# MCU063B_EtherNET.net
KiCad netlist of a schematic drawn in Altium Designer
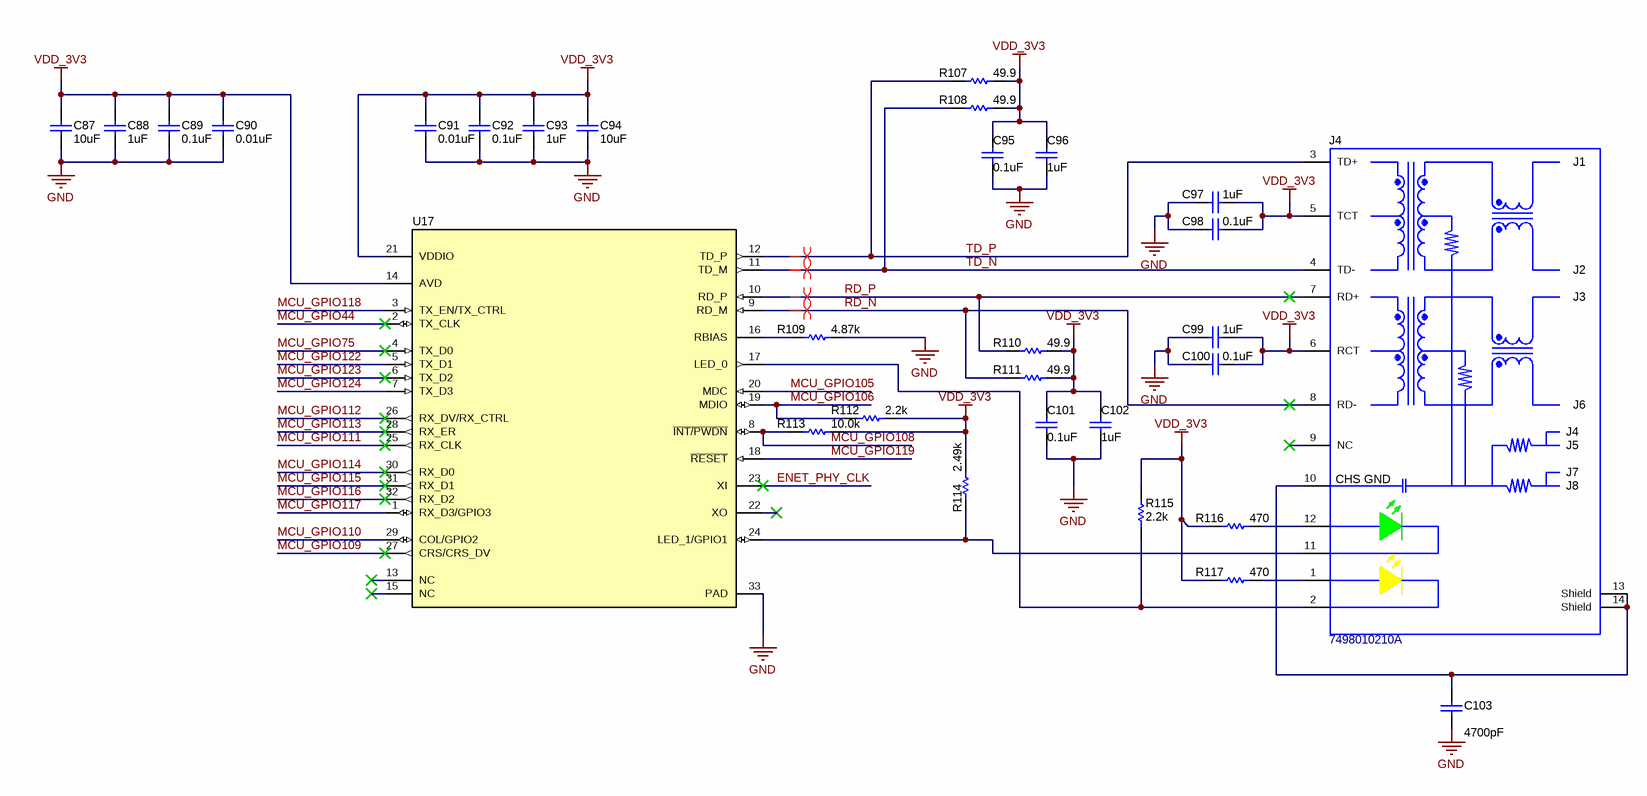
[diagram p0: MCU063B_EtherNET.SchDoc]

(export (version "E")
  (design (tool "Eeschema 10.0.6"))
  (components
    (comp (ref "C87")
      (value "CL05A106MQ5NUNC")
      (footprint "0402")
      (description "CAP, CERM, 10 uF, 6.3 V, +/- 20%, X5R, 0402")
      (fields
        (field (name "MANUFACTURER") "Samsung Electro-Mechanics")
        (field (name "VALUEDISPLAYED") "10uF")
        (field (name "PUBLISHER") "Texas Instruments")
      )
      (libsource (lib "Altium Vault - TI") (part "Capacitor"))
    )
    (comp (ref "C88")
      (value "EMK105BJ105KVHF")
      (footprint "0402")
      (description "CAP, CERM, 1 uF, 16 V, +/- 10%, X5R, 0402")
      (fields
        (field (name "MANUFACTURER") "Taiyo Yuden")
        (field (name "VALUEDISPLAYED") "1uF")
        (field (name "PUBLISHER") "Texas Instruments")
      )
      (libsource (lib "Altium Vault - TI") (part "Capacitor"))
    )
    (comp (ref "C89")
      (value "LMK105BJ104KV-F")
      (footprint "0402")
      (description "CAP, CERM, 0.1 uF, 10 V,+/- 10%, X5R, 0402")
      (fields
        (field (name "MANUFACTURER") "Taiyo Yuden")
        (field (name "VALUEDISPLAYED") "0.1uF")
        (field (name "PUBLISHER") "Texas Instruments")
      )
      (libsource (lib "Altium Vault - TI") (part "Capacitor"))
    )
    (comp (ref "C90")
      (value "885012205031")
      (footprint "0402")
      (description "CAP, CERM, 0.01 uF, 16 V, +/- 10%, X7R, 0402")
      (fields
        (field (name "MANUFACTURER") "Wurth Elektronik")
        (field (name "VALUEDISPLAYED") "0.01uF")
        (field (name "PUBLISHER") "Texas Instruments")
      )
      (libsource (lib "Altium Vault - TI") (part "Capacitor"))
    )
    (comp (ref "C91")
      (value "885012205031")
      (footprint "0402")
      (description "CAP, CERM, 0.01 uF, 16 V, +/- 10%, X7R, 0402")
      (fields
        (field (name "MANUFACTURER") "Wurth Elektronik")
        (field (name "VALUEDISPLAYED") "0.01uF")
        (field (name "PUBLISHER") "Texas Instruments")
      )
      (libsource (lib "Altium Vault - TI") (part "Capacitor"))
    )
    (comp (ref "C92")
      (value "LMK105BJ104KV-F")
      (footprint "0402")
      (description "CAP, CERM, 0.1 uF, 10 V,+/- 10%, X5R, 0402")
      (fields
        (field (name "MANUFACTURER") "Taiyo Yuden")
        (field (name "VALUEDISPLAYED") "0.1uF")
        (field (name "PUBLISHER") "Texas Instruments")
      )
      (libsource (lib "Altium Vault - TI") (part "Capacitor"))
    )
    (comp (ref "C93")
      (value "EMK105BJ105KVHF")
      (footprint "0402")
      (description "CAP, CERM, 1 uF, 16 V, +/- 10%, X5R, 0402")
      (fields
        (field (name "MANUFACTURER") "Taiyo Yuden")
        (field (name "VALUEDISPLAYED") "1uF")
        (field (name "PUBLISHER") "Texas Instruments")
      )
      (libsource (lib "Altium Vault - TI") (part "Capacitor"))
    )
    (comp (ref "C94")
      (value "CL05A106MQ5NUNC")
      (footprint "0402")
      (description "CAP, CERM, 10 uF, 6.3 V, +/- 20%, X5R, 0402")
      (fields
        (field (name "MANUFACTURER") "Samsung Electro-Mechanics")
        (field (name "VALUEDISPLAYED") "10uF")
        (field (name "PUBLISHER") "Texas Instruments")
      )
      (libsource (lib "Altium Vault - TI") (part "Capacitor"))
    )
    (comp (ref "C95")
      (value "LMK105BJ104KV-F")
      (footprint "0402")
      (description "CAP, CERM, 0.1 uF, 10 V,+/- 10%, X5R, 0402")
      (fields
        (field (name "MANUFACTURER") "Taiyo Yuden")
        (field (name "VALUEDISPLAYED") "0.1uF")
        (field (name "PUBLISHER") "Texas Instruments")
      )
      (libsource (lib "Altium Vault - TI") (part "Capacitor"))
    )
    (comp (ref "C96")
      (value "EMK105BJ105KVHF")
      (footprint "0402")
      (description "CAP, CERM, 1 uF, 16 V, +/- 10%, X5R, 0402")
      (fields
        (field (name "MANUFACTURER") "Taiyo Yuden")
        (field (name "VALUEDISPLAYED") "1uF")
        (field (name "PUBLISHER") "Texas Instruments")
      )
      (libsource (lib "Altium Vault - TI") (part "Capacitor"))
    )
    (comp (ref "C97")
      (value "EMK105BJ105KVHF")
      (footprint "0402")
      (description "CAP, CERM, 1 uF, 16 V, +/- 10%, X5R, 0402")
      (fields
        (field (name "MANUFACTURER") "Taiyo Yuden")
        (field (name "VALUEDISPLAYED") "1uF")
        (field (name "PUBLISHER") "Texas Instruments")
      )
      (libsource (lib "Altium Vault - TI") (part "Capacitor"))
    )
    (comp (ref "C98")
      (value "LMK105BJ104KV-F")
      (footprint "0402")
      (description "CAP, CERM, 0.1 uF, 10 V,+/- 10%, X5R, 0402")
      (fields
        (field (name "MANUFACTURER") "Taiyo Yuden")
        (field (name "VALUEDISPLAYED") "0.1uF")
        (field (name "PUBLISHER") "Texas Instruments")
      )
      (libsource (lib "Altium Vault - TI") (part "Capacitor"))
    )
    (comp (ref "C99")
      (value "EMK105BJ105KVHF")
      (footprint "0402")
      (description "CAP, CERM, 1 uF, 16 V, +/- 10%, X5R, 0402")
      (fields
        (field (name "MANUFACTURER") "Taiyo Yuden")
        (field (name "VALUEDISPLAYED") "1uF")
        (field (name "PUBLISHER") "Texas Instruments")
      )
      (libsource (lib "Altium Vault - TI") (part "Capacitor"))
    )
    (comp (ref "C100")
      (value "LMK105BJ104KV-F")
      (footprint "0402")
      (description "CAP, CERM, 0.1 uF, 10 V,+/- 10%, X5R, 0402")
      (fields
        (field (name "MANUFACTURER") "Taiyo Yuden")
        (field (name "VALUEDISPLAYED") "0.1uF")
        (field (name "PUBLISHER") "Texas Instruments")
      )
      (libsource (lib "Altium Vault - TI") (part "Capacitor"))
    )
    (comp (ref "C101")
      (value "LMK105BJ104KV-F")
      (footprint "0402")
      (description "CAP, CERM, 0.1 uF, 10 V,+/- 10%, X5R, 0402")
      (fields
        (field (name "MANUFACTURER") "Taiyo Yuden")
        (field (name "VALUEDISPLAYED") "0.1uF")
        (field (name "PUBLISHER") "Texas Instruments")
      )
      (libsource (lib "Altium Vault - TI") (part "Capacitor"))
    )
    (comp (ref "C102")
      (value "EMK105BJ105KVHF")
      (footprint "0402")
      (description "CAP, CERM, 1 uF, 16 V, +/- 10%, X5R, 0402")
      (fields
        (field (name "MANUFACTURER") "Taiyo Yuden")
        (field (name "VALUEDISPLAYED") "1uF")
        (field (name "PUBLISHER") "Texas Instruments")
      )
      (libsource (lib "Altium Vault - TI") (part "Capacitor"))
    )
    (comp (ref "C103")
      (value "12061C472KAT2A")
      (footprint "1206")
      (description "CAP, CERM, 4700 pF, 100 V, +/- 10%, X7R, 1206")
      (fields
        (field (name "MANUFACTURER") "AVX")
        (field (name "VALUEDISPLAYED") "4700pF")
        (field (name "PUBLISHER") "Texas Instruments")
      )
      (libsource (lib "Altium Vault - TI") (part "Capacitor"))
    )
    (comp (ref "J4")
      (value "7498010210A")
      (footprint "Wurth_7498010210A")
      (description "Connector, RJ45, 1x1, Gold, R/A, SMT")
      (fields (field (name "MANUFACTURER") "Wurth Elektronik"))
      (libsource (lib "Altium Vault - TI") (part "Wurth_7498010210A"))
    )
    (comp (ref "R107")
      (value "RC0402FR-0749R9L")
      (footprint "0402")
      (description "RES, 49.9, 1%, 0.063 W, 0402")
      (fields
        (field (name "MANUFACTURER") "Yageo America")
        (field (name "VALUEDISPLAYED") "49.9")
        (field (name "PUBLISHER") "Texas Instruments")
      )
      (libsource (lib "Altium Vault - TI") (part "Resistor"))
    )
    (comp (ref "R108")
      (value "RC0402FR-0749R9L")
      (footprint "0402")
      (description "RES, 49.9, 1%, 0.063 W, 0402")
      (fields
        (field (name "MANUFACTURER") "Yageo America")
        (field (name "VALUEDISPLAYED") "49.9")
        (field (name "PUBLISHER") "Texas Instruments")
      )
      (libsource (lib "Altium Vault - TI") (part "Resistor"))
    )
    (comp (ref "R109")
      (value "CRCW04024K87FKED")
      (footprint "0402")
      (description "RES, 4.87 k, 1%, 0.063 W, AEC-Q200 Grade 0, 0402")
      (fields (field (name "MANUFACTURER") "Vishay-Dale") (field (name "VALUEDISPLAYED") "4.87k"))
      (libsource (lib "Altium Vault - TI") (part "Resistor"))
    )
    (comp (ref "R110")
      (value "RC0402FR-0749R9L")
      (footprint "0402")
      (description "RES, 49.9, 1%, 0.063 W, 0402")
      (fields
        (field (name "MANUFACTURER") "Yageo America")
        (field (name "VALUEDISPLAYED") "49.9")
        (field (name "PUBLISHER") "Texas Instruments")
      )
      (libsource (lib "Altium Vault - TI") (part "Resistor"))
    )
    (comp (ref "R111")
      (value "RC0402FR-0749R9L")
      (footprint "0402")
      (description "RES, 49.9, 1%, 0.063 W, 0402")
      (fields
        (field (name "MANUFACTURER") "Yageo America")
        (field (name "VALUEDISPLAYED") "49.9")
        (field (name "PUBLISHER") "Texas Instruments")
      )
      (libsource (lib "Altium Vault - TI") (part "Resistor"))
    )
    (comp (ref "R112")
      (value "CRCW04022K20JNED")
      (footprint "0402")
      (description "RES, 2.2 k, 5%, 0.063 W, AEC-Q200 Grade 0, 0402")
      (fields (field (name "MANUFACTURER") "Vishay-Dale") (field (name "VALUEDISPLAYED") "2.2k"))
      (libsource (lib "Altium Vault - TI") (part "Resistor"))
    )
    (comp (ref "R113")
      (value "RC0402FR-0710KL")
      (footprint "0402")
      (description "RES, 10.0 k, 1%, 0.063 W, 0402")
      (fields (field (name "MANUFACTURER") "Yageo America") (field (name "VALUEDISPLAYED") "10.0k"))
      (libsource (lib "Altium Vault - TI") (part "Resistor"))
    )
    (comp (ref "R114")
      (value "CRCW04022K49FKED")
      (footprint "0402")
      (description "RES, 2.49 k, 1%, 0.063 W, AEC-Q200 Grade 0, 0402")
      (fields (field (name "MANUFACTURER") "Vishay-Dale") (field (name "VALUEDISPLAYED") "2.49k"))
      (libsource (lib "Altium Vault - TI") (part "Resistor"))
    )
    (comp (ref "R115")
      (value "CRCW04022K20JNED")
      (footprint "0402")
      (description "RES, 2.2 k, 5%, 0.063 W, AEC-Q200 Grade 0, 0402")
      (fields (field (name "MANUFACTURER") "Vishay-Dale") (field (name "VALUEDISPLAYED") "2.2k"))
      (libsource (lib "Altium Vault - TI") (part "Resistor"))
    )
    (comp (ref "R116")
      (value "CRCW0603470RJNEA")
      (footprint "0603")
      (description "RES, 470, 5%, 0.1 W, AEC-Q200 Grade 0, 0603")
      (fields (field (name "MANUFACTURER") "Vishay-Dale") (field (name "VALUEDISPLAYED") "470"))
      (libsource (lib "Altium Vault - TI") (part "Resistor"))
    )
    (comp (ref "R117")
      (value "CRCW0603470RJNEA")
      (footprint "0603")
      (description "RES, 470, 5%, 0.1 W, AEC-Q200 Grade 0, 0603")
      (fields (field (name "MANUFACTURER") "Vishay-Dale") (field (name "VALUEDISPLAYED") "470"))
      (libsource (lib "Altium Vault - TI") (part "Resistor"))
    )
    (comp (ref "U17")
      (value "DP83822IRHBR")
      (footprint "RHB0032B")
      (description "Robust, Low Power 10/100 Ethernet Physical Layer Transceiver, RHB0032B (VQFN-32)")
      (fields
        (field (name "ALTERNATE PARTNUMBER") "DP83822IRHBT")
        (field (name "MANUFACTURER") "Texas Instruments")
      )
      (libsource (lib "Altium Vault - TI") (part "DP83822"))
    )
  )
  (nets
    (net (code "1") (name "/ENET_PHY_CLK") (class "Default")
      (node (ref "U17") (pin "23") (pinfunction "XI_23") (pintype "passive+no_connect"))
    )
    (net (code "2") (name "/MCU_GPIO44") (class "Default")
      (node (ref "U17") (pin "2") (pinfunction "TX_CLK_2") (pintype "bidirectional+no_connect"))
    )
    (net (code "3") (name "/MCU_GPIO75") (class "Default")
      (node (ref "U17") (pin "4") (pinfunction "TX_D0_4") (pintype "input+no_connect"))
    )
    (net (code "4") (name "/MCU_GPIO105") (class "Default")
      (node (ref "U17") (pin "20") (pinfunction "MDC_20") (pintype "input"))
    )
    (net (code "5") (name "/MCU_GPIO106") (class "Default")
      (node (ref "R112") (pin "2") (pinfunction "2_2") (pintype "passive"))
      (node (ref "U17") (pin "19") (pinfunction "MDIO_19") (pintype "bidirectional"))
    )
    (net (code "6") (name "/MCU_GPIO108") (class "Default")
      (node (ref "R113") (pin "1") (pinfunction "1_1") (pintype "passive"))
      (node (ref "U17") (pin "8") (pinfunction "INT/PWDN_8") (pintype "bidirectional"))
    )
    (net (code "7") (name "/MCU_GPIO109") (class "Default")
      (node (ref "U17") (pin "27") (pinfunction "CRS/CRS_DV_27") (pintype "output+no_connect"))
    )
    (net (code "8") (name "/MCU_GPIO110") (class "Default")
      (node (ref "U17") (pin "29") (pinfunction "COL/GPIO2_29") (pintype "bidirectional"))
    )
    (net (code "9") (name "/MCU_GPIO111") (class "Default")
      (node (ref "U17") (pin "25") (pinfunction "RX_CLK_25") (pintype "output+no_connect"))
    )
    (net (code "10") (name "/MCU_GPIO112") (class "Default")
      (node (ref "U17") (pin "26") (pinfunction "RX_DV/RX_CTRL_26") (pintype "output+no_connect"))
    )
    (net (code "11") (name "/MCU_GPIO113") (class "Default")
      (node (ref "U17") (pin "28") (pinfunction "RX_ER_28") (pintype "output+no_connect"))
    )
    (net (code "12") (name "/MCU_GPIO114") (class "Default")
      (node (ref "U17") (pin "30") (pinfunction "RX_D0_30") (pintype "output+no_connect"))
    )
    (net (code "13") (name "/MCU_GPIO115") (class "Default")
      (node (ref "U17") (pin "31") (pinfunction "RX_D1_31") (pintype "output+no_connect"))
    )
    (net (code "14") (name "/MCU_GPIO116") (class "Default")
      (node (ref "U17") (pin "32") (pinfunction "RX_D2_32") (pintype "output+no_connect"))
    )
    (net (code "15") (name "/MCU_GPIO117") (class "Default")
      (node (ref "U17") (pin "1") (pinfunction "RX_D3/GPIO3_1") (pintype "bidirectional"))
    )
    (net (code "16") (name "/MCU_GPIO118") (class "Default")
      (node (ref "U17") (pin "3") (pinfunction "TX_EN/TX_CTRL_3") (pintype "input"))
    )
    (net (code "17") (name "/MCU_GPIO119") (class "Default")
      (node (ref "U17") (pin "18") (pinfunction "RESET_18") (pintype "input"))
    )
    (net (code "18") (name "/MCU_GPIO122") (class "Default")
      (node (ref "U17") (pin "5") (pinfunction "TX_D1_5") (pintype "input"))
    )
    (net (code "19") (name "/MCU_GPIO123") (class "Default")
      (node (ref "U17") (pin "6") (pinfunction "TX_D2_6") (pintype "input+no_connect"))
    )
    (net (code "20") (name "/MCU_GPIO124") (class "Default")
      (node (ref "U17") (pin "7") (pinfunction "TX_D3_7") (pintype "input"))
    )
    (net (code "21") (name "/RD_N") (class "Default")
      (node (ref "J4") (pin "8") (pinfunction "RD-_8") (pintype "passive"))
      (node (ref "R111") (pin "1") (pinfunction "1_1") (pintype "passive"))
      (node (ref "U17") (pin "9") (pinfunction "RD_M_9") (pintype "input"))
    )
    (net (code "22") (name "/RD_P") (class "Default")
      (node (ref "J4") (pin "7") (pinfunction "RD+_7") (pintype "passive"))
      (node (ref "R110") (pin "1") (pinfunction "1_1") (pintype "passive"))
      (node (ref "U17") (pin "10") (pinfunction "RD_P_10") (pintype "input"))
    )
    (net (code "23") (name "/TD_N") (class "Default")
      (node (ref "J4") (pin "4") (pinfunction "TD-_4") (pintype "passive"))
      (node (ref "R108") (pin "1") (pinfunction "1_1") (pintype "passive"))
      (node (ref "U17") (pin "11") (pinfunction "TD_M_11") (pintype "output"))
    )
    (net (code "24") (name "/TD_P") (class "Default")
      (node (ref "J4") (pin "3") (pinfunction "TD+_3") (pintype "passive"))
      (node (ref "R107") (pin "1") (pinfunction "1_1") (pintype "passive"))
      (node (ref "U17") (pin "12") (pinfunction "TD_P_12") (pintype "output"))
    )
    (net (code "25") (name "GND") (class "Default")
      (node (ref "C100") (pin "1") (pinfunction "1_1") (pintype "passive"))
      (node (ref "C101") (pin "2") (pinfunction "2_2") (pintype "passive"))
      (node (ref "C102") (pin "2") (pinfunction "2_2") (pintype "passive"))
      (node (ref "C103") (pin "1") (pinfunction "1_1") (pintype "passive"))
      (node (ref "C87") (pin "2") (pinfunction "2_2") (pintype "passive"))
      (node (ref "C88") (pin "2") (pinfunction "2_2") (pintype "passive"))
      (node (ref "C89") (pin "2") (pinfunction "2_2") (pintype "passive"))
      (node (ref "C90") (pin "2") (pinfunction "2_2") (pintype "passive"))
      (node (ref "C91") (pin "2") (pinfunction "2_2") (pintype "passive"))
      (node (ref "C92") (pin "2") (pinfunction "2_2") (pintype "passive"))
      (node (ref "C93") (pin "2") (pinfunction "2_2") (pintype "passive"))
      (node (ref "C94") (pin "2") (pinfunction "2_2") (pintype "passive"))
      (node (ref "C95") (pin "2") (pinfunction "2_2") (pintype "passive"))
      (node (ref "C96") (pin "2") (pinfunction "2_2") (pintype "passive"))
      (node (ref "C97") (pin "1") (pinfunction "1_1") (pintype "passive"))
      (node (ref "C98") (pin "1") (pinfunction "1_1") (pintype "passive"))
      (node (ref "C99") (pin "1") (pinfunction "1_1") (pintype "passive"))
      (node (ref "R109") (pin "2") (pinfunction "2_2") (pintype "passive"))
      (node (ref "U17") (pin "33") (pinfunction "PAD_33") (pintype "power_in"))
    )
    (net (code "26") (name "Net-(J4-CHS_GND)") (class "Default")
      (node (ref "C103") (pin "2") (pinfunction "2_2") (pintype "passive"))
      (node (ref "J4") (pin "10") (pinfunction "CHS_GND_10") (pintype "power_in"))
      (node (ref "J4") (pin "13") (pinfunction "Shield_13") (pintype "passive"))
      (node (ref "J4") (pin "14") (pinfunction "Shield_14") (pintype "passive"))
    )
    (net (code "27") (name "Net-(J4-LEFT_LED_ANODE)") (class "Default")
      (node (ref "J4") (pin "12") (pinfunction "LEFT_LED_ANODE_12") (pintype "passive"))
      (node (ref "R116") (pin "2") (pinfunction "2_2") (pintype "passive"))
    )
    (net (code "28") (name "Net-(J4-LEFT_LED_CATHODE)") (class "Default")
      (node (ref "J4") (pin "11") (pinfunction "LEFT_LED_CATHODE_11") (pintype "passive"))
      (node (ref "R114") (pin "1") (pinfunction "1_1") (pintype "passive"))
      (node (ref "U17") (pin "24") (pinfunction "LED_1/GPIO1_24") (pintype "bidirectional"))
    )
    (net (code "29") (name "Net-(J4-RIGHT_LED_ANODE)") (class "Default")
      (node (ref "J4") (pin "1") (pinfunction "RIGHT_LED_ANODE_1") (pintype "passive"))
      (node (ref "R117") (pin "2") (pinfunction "2_2") (pintype "passive"))
    )
    (net (code "30") (name "Net-(J4-RIGHT_LED_CATHODE)") (class "Default")
      (node (ref "J4") (pin "2") (pinfunction "RIGHT_LED_CATHODE_2") (pintype "passive"))
      (node (ref "R115") (pin "1") (pinfunction "1_1") (pintype "passive"))
      (node (ref "U17") (pin "17") (pinfunction "LED_0_17") (pintype "output"))
    )
    (net (code "31") (name "Net-(U17-RBIAS)") (class "Default")
      (node (ref "R109") (pin "1") (pinfunction "1_1") (pintype "passive"))
      (node (ref "U17") (pin "16") (pinfunction "RBIAS_16") (pintype "passive"))
    )
    (net (code "32") (name "VDD_3V3") (class "Default")
      (node (ref "C100") (pin "2") (pinfunction "2_2") (pintype "passive"))
      (node (ref "C101") (pin "1") (pinfunction "1_1") (pintype "passive"))
      (node (ref "C102") (pin "1") (pinfunction "1_1") (pintype "passive"))
      (node (ref "C87") (pin "1") (pinfunction "1_1") (pintype "passive"))
      (node (ref "C88") (pin "1") (pinfunction "1_1") (pintype "passive"))
      (node (ref "C89") (pin "1") (pinfunction "1_1") (pintype "passive"))
      (node (ref "C90") (pin "1") (pinfunction "1_1") (pintype "passive"))
      (node (ref "C91") (pin "1") (pinfunction "1_1") (pintype "passive"))
      (node (ref "C92") (pin "1") (pinfunction "1_1") (pintype "passive"))
      (node (ref "C93") (pin "1") (pinfunction "1_1") (pintype "passive"))
      (node (ref "C94") (pin "1") (pinfunction "1_1") (pintype "passive"))
      (node (ref "C95") (pin "1") (pinfunction "1_1") (pintype "passive"))
      (node (ref "C96") (pin "1") (pinfunction "1_1") (pintype "passive"))
      (node (ref "C97") (pin "2") (pinfunction "2_2") (pintype "passive"))
      (node (ref "C98") (pin "2") (pinfunction "2_2") (pintype "passive"))
      (node (ref "C99") (pin "2") (pinfunction "2_2") (pintype "passive"))
      (node (ref "J4") (pin "5") (pinfunction "TCT_5") (pintype "passive"))
      (node (ref "J4") (pin "6") (pinfunction "RCT_6") (pintype "passive"))
      (node (ref "R107") (pin "2") (pinfunction "2_2") (pintype "passive"))
      (node (ref "R108") (pin "2") (pinfunction "2_2") (pintype "passive"))
      (node (ref "R110") (pin "2") (pinfunction "2_2") (pintype "passive"))
      (node (ref "R111") (pin "2") (pinfunction "2_2") (pintype "passive"))
      (node (ref "R112") (pin "1") (pinfunction "1_1") (pintype "passive"))
      (node (ref "R113") (pin "2") (pinfunction "2_2") (pintype "passive"))
      (node (ref "R114") (pin "2") (pinfunction "2_2") (pintype "passive"))
      (node (ref "R115") (pin "2") (pinfunction "2_2") (pintype "passive"))
      (node (ref "R116") (pin "1") (pinfunction "1_1") (pintype "passive"))
      (node (ref "R117") (pin "1") (pinfunction "1_1") (pintype "passive"))
      (node (ref "U17") (pin "14") (pinfunction "AVD_14") (pintype "power_in"))
      (node (ref "U17") (pin "21") (pinfunction "VDDIO_21") (pintype "power_in"))
    )
    (net (code "33") (name "unconnected-(J4-NC-Pad9)") (class "Default")
      (node (ref "J4") (pin "9") (pinfunction "NC_9") (pintype "passive+no_connect"))
    )
    (net (code "34") (name "unconnected-(U17-NC-Pad13)") (class "Default")
      (node (ref "U17") (pin "13") (pinfunction "NC_13") (pintype "passive+no_connect"))
    )
    (net (code "35") (name "unconnected-(U17-NC-Pad15)") (class "Default")
      (node (ref "U17") (pin "15") (pinfunction "NC_15") (pintype "passive+no_connect"))
    )
    (net (code "36") (name "unconnected-(U17-XO-Pad22)") (class "Default")
      (node (ref "U17") (pin "22") (pinfunction "XO_22") (pintype "passive+no_connect"))
    )
  )
)
